# Sheet1.net
KiCad netlist of a schematic drawn in Altium Designer
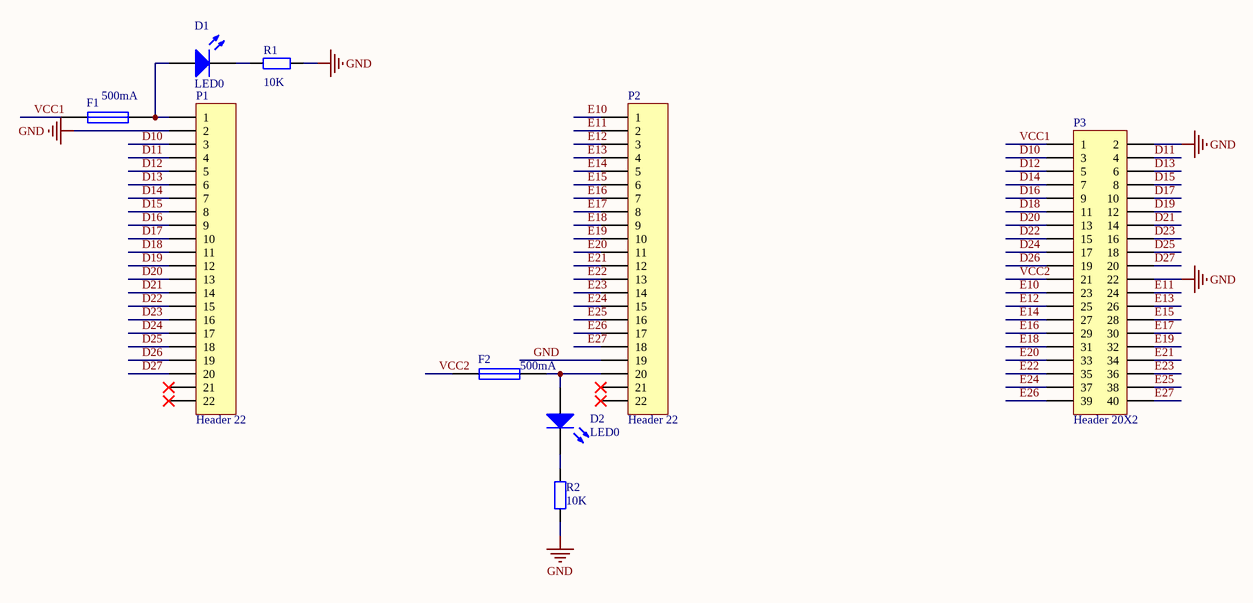
[diagram p0: Sheet1.SchDoc]

(export (version "E")
  (design (tool "Eeschema 10.0.6"))
  (components
    (comp (ref "D1")
      (value "LED0")
      (footprint "LED0805绿")
      (description "Typical INFRARED GaAs LED")
      (fields (field (name "PUBLISHER") "Altium Limited"))
      (libsource (lib "Miscellaneous Devices") (part "LED0"))
    )
    (comp (ref "D2")
      (value "LED0")
      (footprint "LED0805绿")
      (description "Typical INFRARED GaAs LED")
      (fields (field (name "PUBLISHER") "Altium Limited"))
      (libsource (lib "Miscellaneous Devices") (part "LED0"))
    )
    (comp (ref "F1")
      (value "500mA")
      (footprint "R0805")
      (description "Fuse")
      (fields (field (name "PUBLISHER") "Altium Limited"))
      (libsource (lib "Miscellaneous Devices") (part "Fuse 1"))
    )
    (comp (ref "F2")
      (value "500mA")
      (footprint "R0805")
      (description "Fuse")
      (fields (field (name "PUBLISHER") "Altium Limited"))
      (libsource (lib "Miscellaneous Devices") (part "Fuse 1"))
    )
    (comp (ref "P1")
      (value "Header 22")
      (footprint "FPC20Pin")
      (description "Header, 22-Pin")
      (fields (field (name "PUBLISHER") "Altium Limited"))
      (libsource (lib "Miscellaneous Connectors") (part "Header 22"))
    )
    (comp (ref "P2")
      (value "Header 22")
      (footprint "FPC20Pin")
      (description "Header, 22-Pin")
      (fields (field (name "PUBLISHER") "Altium Limited"))
      (libsource (lib "Miscellaneous Connectors") (part "Header 22"))
    )
    (comp (ref "P3")
      (value "Header 20X2")
      (footprint "BTB0.8con40Pin")
      (description "Header, 20-Pin, Dual row")
      (fields (field (name "PUBLISHER") "Altium Limited"))
      (libsource (lib "Miscellaneous Connectors") (part "Header 20X2"))
    )
    (comp (ref "R1")
      (value "10K")
      (footprint "R0805")
      (description "Resistor")
      (fields (field (name "Comment") "Res2") (field (name "PUBLISHER") "Altium Limited"))
      (libsource (lib "Miscellaneous Devices") (part "Res2"))
    )
    (comp (ref "R2")
      (value "10K")
      (footprint "R0805")
      (description "Resistor")
      (fields (field (name "Comment") "Res2") (field (name "PUBLISHER") "Altium Limited"))
      (libsource (lib "") (part "Res2_1"))
    )
  )
  (nets
    (net (code "1") (name "/D10") (class "Default")
      (node (ref "P1") (pin "3") (pinfunction "3_3") (pintype "passive"))
      (node (ref "P3") (pin "3") (pinfunction "3_3") (pintype "passive"))
    )
    (net (code "2") (name "/D11") (class "Default")
      (node (ref "P1") (pin "4") (pinfunction "4_4") (pintype "passive"))
      (node (ref "P3") (pin "4") (pinfunction "4_4") (pintype "passive"))
    )
    (net (code "3") (name "/D12") (class "Default")
      (node (ref "P1") (pin "5") (pinfunction "5_5") (pintype "passive"))
      (node (ref "P3") (pin "5") (pinfunction "5_5") (pintype "passive"))
    )
    (net (code "4") (name "/D13") (class "Default")
      (node (ref "P1") (pin "6") (pinfunction "6_6") (pintype "passive"))
      (node (ref "P3") (pin "6") (pinfunction "6_6") (pintype "passive"))
    )
    (net (code "5") (name "/D14") (class "Default")
      (node (ref "P1") (pin "7") (pinfunction "7_7") (pintype "passive"))
      (node (ref "P3") (pin "7") (pinfunction "7_7") (pintype "passive"))
    )
    (net (code "6") (name "/D15") (class "Default")
      (node (ref "P1") (pin "8") (pinfunction "8_8") (pintype "passive"))
      (node (ref "P3") (pin "8") (pinfunction "8_8") (pintype "passive"))
    )
    (net (code "7") (name "/D16") (class "Default")
      (node (ref "P1") (pin "9") (pinfunction "9_9") (pintype "passive"))
      (node (ref "P3") (pin "9") (pinfunction "9_9") (pintype "passive"))
    )
    (net (code "8") (name "/D17") (class "Default")
      (node (ref "P1") (pin "10") (pinfunction "10_10") (pintype "passive"))
      (node (ref "P3") (pin "10") (pinfunction "10_10") (pintype "passive"))
    )
    (net (code "9") (name "/D18") (class "Default")
      (node (ref "P1") (pin "11") (pinfunction "11_11") (pintype "passive"))
      (node (ref "P3") (pin "11") (pinfunction "11_11") (pintype "passive"))
    )
    (net (code "10") (name "/D19") (class "Default")
      (node (ref "P1") (pin "12") (pinfunction "12_12") (pintype "passive"))
      (node (ref "P3") (pin "12") (pinfunction "12_12") (pintype "passive"))
    )
    (net (code "11") (name "/D20") (class "Default")
      (node (ref "P1") (pin "13") (pinfunction "13_13") (pintype "passive"))
      (node (ref "P3") (pin "13") (pinfunction "13_13") (pintype "passive"))
    )
    (net (code "12") (name "/D21") (class "Default")
      (node (ref "P1") (pin "14") (pinfunction "14_14") (pintype "passive"))
      (node (ref "P3") (pin "14") (pinfunction "14_14") (pintype "passive"))
    )
    (net (code "13") (name "/D22") (class "Default")
      (node (ref "P1") (pin "15") (pinfunction "15_15") (pintype "passive"))
      (node (ref "P3") (pin "15") (pinfunction "15_15") (pintype "passive"))
    )
    (net (code "14") (name "/D23") (class "Default")
      (node (ref "P1") (pin "16") (pinfunction "16_16") (pintype "passive"))
      (node (ref "P3") (pin "16") (pinfunction "16_16") (pintype "passive"))
    )
    (net (code "15") (name "/D24") (class "Default")
      (node (ref "P1") (pin "17") (pinfunction "17_17") (pintype "passive"))
      (node (ref "P3") (pin "17") (pinfunction "17_17") (pintype "passive"))
    )
    (net (code "16") (name "/D25") (class "Default")
      (node (ref "P1") (pin "18") (pinfunction "18_18") (pintype "passive"))
      (node (ref "P3") (pin "18") (pinfunction "18_18") (pintype "passive"))
    )
    (net (code "17") (name "/D26") (class "Default")
      (node (ref "P1") (pin "19") (pinfunction "19_19") (pintype "passive"))
      (node (ref "P3") (pin "19") (pinfunction "19_19") (pintype "passive"))
    )
    (net (code "18") (name "/D27") (class "Default")
      (node (ref "P1") (pin "20") (pinfunction "20_20") (pintype "passive"))
      (node (ref "P3") (pin "20") (pinfunction "20_20") (pintype "passive"))
    )
    (net (code "19") (name "/E10") (class "Default")
      (node (ref "P2") (pin "1") (pinfunction "1_1") (pintype "passive"))
      (node (ref "P3") (pin "23") (pinfunction "23_23") (pintype "passive"))
    )
    (net (code "20") (name "/E11") (class "Default")
      (node (ref "P2") (pin "2") (pinfunction "2_2") (pintype "passive"))
      (node (ref "P3") (pin "24") (pinfunction "24_24") (pintype "passive"))
    )
    (net (code "21") (name "/E12") (class "Default")
      (node (ref "P2") (pin "3") (pinfunction "3_3") (pintype "passive"))
      (node (ref "P3") (pin "25") (pinfunction "25_25") (pintype "passive"))
    )
    (net (code "22") (name "/E13") (class "Default")
      (node (ref "P2") (pin "4") (pinfunction "4_4") (pintype "passive"))
      (node (ref "P3") (pin "26") (pinfunction "26_26") (pintype "passive"))
    )
    (net (code "23") (name "/E14") (class "Default")
      (node (ref "P2") (pin "5") (pinfunction "5_5") (pintype "passive"))
      (node (ref "P3") (pin "27") (pinfunction "27_27") (pintype "passive"))
    )
    (net (code "24") (name "/E15") (class "Default")
      (node (ref "P2") (pin "6") (pinfunction "6_6") (pintype "passive"))
      (node (ref "P3") (pin "28") (pinfunction "28_28") (pintype "passive"))
    )
    (net (code "25") (name "/E16") (class "Default")
      (node (ref "P2") (pin "7") (pinfunction "7_7") (pintype "passive"))
      (node (ref "P3") (pin "29") (pinfunction "29_29") (pintype "passive"))
    )
    (net (code "26") (name "/E17") (class "Default")
      (node (ref "P2") (pin "8") (pinfunction "8_8") (pintype "passive"))
      (node (ref "P3") (pin "30") (pinfunction "30_30") (pintype "passive"))
    )
    (net (code "27") (name "/E18") (class "Default")
      (node (ref "P2") (pin "9") (pinfunction "9_9") (pintype "passive"))
      (node (ref "P3") (pin "31") (pinfunction "31_31") (pintype "passive"))
    )
    (net (code "28") (name "/E19") (class "Default")
      (node (ref "P2") (pin "10") (pinfunction "10_10") (pintype "passive"))
      (node (ref "P3") (pin "32") (pinfunction "32_32") (pintype "passive"))
    )
    (net (code "29") (name "/E20") (class "Default")
      (node (ref "P2") (pin "11") (pinfunction "11_11") (pintype "passive"))
      (node (ref "P3") (pin "33") (pinfunction "33_33") (pintype "passive"))
    )
    (net (code "30") (name "/E21") (class "Default")
      (node (ref "P2") (pin "12") (pinfunction "12_12") (pintype "passive"))
      (node (ref "P3") (pin "34") (pinfunction "34_34") (pintype "passive"))
    )
    (net (code "31") (name "/E22") (class "Default")
      (node (ref "P2") (pin "13") (pinfunction "13_13") (pintype "passive"))
      (node (ref "P3") (pin "35") (pinfunction "35_35") (pintype "passive"))
    )
    (net (code "32") (name "/E23") (class "Default")
      (node (ref "P2") (pin "14") (pinfunction "14_14") (pintype "passive"))
      (node (ref "P3") (pin "36") (pinfunction "36_36") (pintype "passive"))
    )
    (net (code "33") (name "/E24") (class "Default")
      (node (ref "P2") (pin "15") (pinfunction "15_15") (pintype "passive"))
      (node (ref "P3") (pin "37") (pinfunction "37_37") (pintype "passive"))
    )
    (net (code "34") (name "/E25") (class "Default")
      (node (ref "P2") (pin "16") (pinfunction "16_16") (pintype "passive"))
      (node (ref "P3") (pin "38") (pinfunction "38_38") (pintype "passive"))
    )
    (net (code "35") (name "/E26") (class "Default")
      (node (ref "P2") (pin "17") (pinfunction "17_17") (pintype "passive"))
      (node (ref "P3") (pin "39") (pinfunction "39_39") (pintype "passive"))
    )
    (net (code "36") (name "/E27") (class "Default")
      (node (ref "P2") (pin "18") (pinfunction "18_18") (pintype "passive"))
      (node (ref "P3") (pin "40") (pinfunction "40_40") (pintype "passive"))
    )
    (net (code "37") (name "/VCC1") (class "Default")
      (node (ref "F1") (pin "1") (pinfunction "1_1") (pintype "passive"))
      (node (ref "P3") (pin "1") (pinfunction "1_1") (pintype "passive"))
    )
    (net (code "38") (name "/VCC2") (class "Default")
      (node (ref "F2") (pin "1") (pinfunction "1_1") (pintype "passive"))
      (node (ref "P3") (pin "21") (pinfunction "21_21") (pintype "passive"))
    )
    (net (code "39") (name "GND") (class "Default")
      (node (ref "P1") (pin "2") (pinfunction "2_2") (pintype "passive"))
      (node (ref "P2") (pin "19") (pinfunction "19_19") (pintype "passive"))
      (node (ref "P3") (pin "2") (pinfunction "2_2") (pintype "passive"))
      (node (ref "P3") (pin "22") (pinfunction "22_22") (pintype "passive"))
      (node (ref "R1") (pin "2") (pinfunction "2_2") (pintype "passive"))
      (node (ref "R2") (pin "1") (pinfunction "1_1") (pintype "passive"))
    )
    (net (code "40") (name "Net-(D1-A)") (class "Default")
      (node (ref "D1") (pin "1") (pinfunction "A_1") (pintype "passive"))
      (node (ref "F1") (pin "2") (pinfunction "2_2") (pintype "passive"))
      (node (ref "P1") (pin "1") (pinfunction "1_1") (pintype "passive"))
    )
    (net (code "41") (name "Net-(D1-K)") (class "Default")
      (node (ref "D1") (pin "2") (pinfunction "K_2") (pintype "passive"))
      (node (ref "R1") (pin "1") (pinfunction "1_1") (pintype "passive"))
    )
    (net (code "42") (name "Net-(D2-A)") (class "Default")
      (node (ref "D2") (pin "1") (pinfunction "A_1") (pintype "passive"))
      (node (ref "F2") (pin "2") (pinfunction "2_2") (pintype "passive"))
      (node (ref "P2") (pin "20") (pinfunction "20_20") (pintype "passive"))
    )
    (net (code "43") (name "Net-(D2-K)") (class "Default")
      (node (ref "D2") (pin "2") (pinfunction "K_2") (pintype "passive"))
      (node (ref "R2") (pin "2") (pinfunction "2_2") (pintype "passive"))
    )
    (net (code "44") (name "unconnected-(P1-Pad21)") (class "Default")
      (node (ref "P1") (pin "21") (pinfunction "21_21") (pintype "passive+no_connect"))
    )
    (net (code "45") (name "unconnected-(P1-Pad22)") (class "Default")
      (node (ref "P1") (pin "22") (pinfunction "22_22") (pintype "passive+no_connect"))
    )
    (net (code "46") (name "unconnected-(P2-Pad21)") (class "Default")
      (node (ref "P2") (pin "21") (pinfunction "21_21") (pintype "passive+no_connect"))
    )
    (net (code "47") (name "unconnected-(P2-Pad22)") (class "Default")
      (node (ref "P2") (pin "22") (pinfunction "22_22") (pintype "passive+no_connect"))
    )
  )
)
